# Motor_Driver.net
KiCad netlist of a schematic drawn in Altium Designer
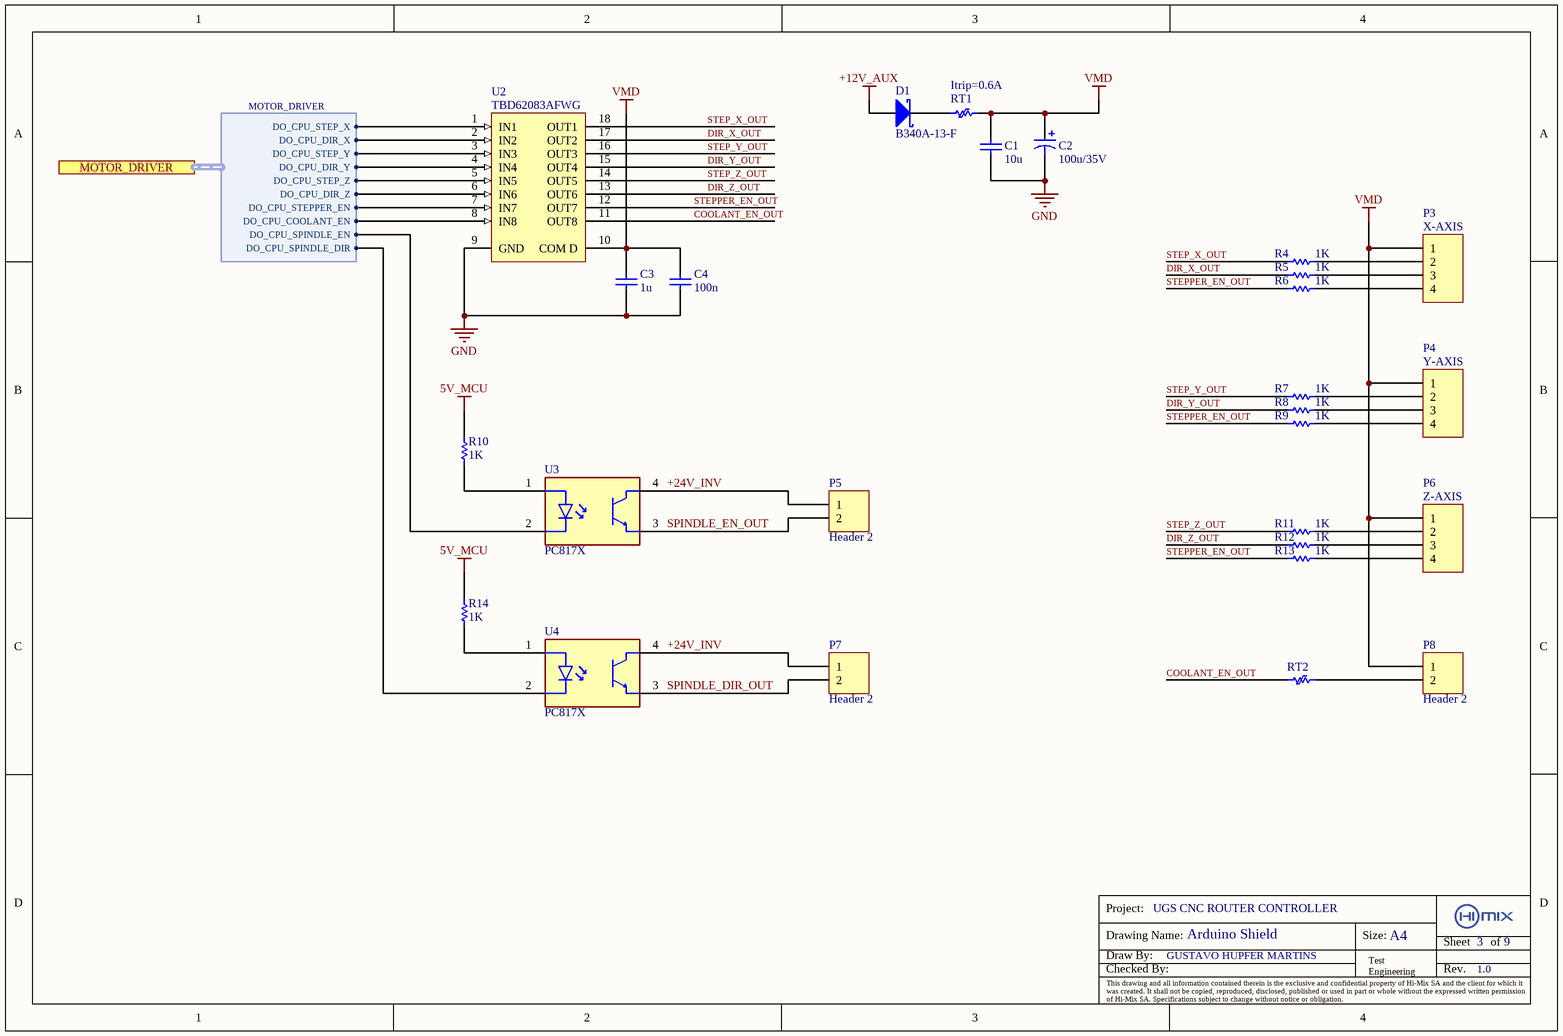
[diagram p0: Motor Driver.SchDoc]

(export (version "E")
  (design (tool "Eeschema 10.0.6"))
  (components
    (comp (ref "C1")
      (value "10u")
      (footprint "SMT1210_M")
      (description "Capacitor")
      (fields (field (name "Comment") "X7R/1210/50V") (field (name "PUBLISHER") "Altium Limited"))
      (libsource (lib "Miscellaneous Devices") (part "Cap"))
    )
    (comp (ref "C2")
      (value "100u/35V")
      (footprint "FKV Panasonic 8x10.2L (F)")
      (description "Polarized Capacitor (Radial)")
      (fields (field (name "Comment") "8x10.2"))
      (libsource (lib "Miscellaneous Devices") (part "Cap Pol1"))
    )
    (comp (ref "C3")
      (value "1u")
      (footprint "SMT0805_N")
      (description "Capacitor")
      (fields (field (name "Comment") "X7R/0805/50V") (field (name "PUBLISHER") "Altium Limited"))
      (libsource (lib "Miscellaneous Devices") (part "Cap"))
    )
    (comp (ref "C4")
      (value "100n")
      (footprint "SMT0603_N")
      (description "Capacitor")
      (fields (field (name "Comment") "X7R/0603/50V") (field (name "PUBLISHER") "Altium Limited"))
      (libsource (lib "Miscellaneous Devices") (part "Cap"))
    )
    (comp (ref "D1")
      (value "B340A-13-F")
      (footprint "SMB")
      (description "Schottky Diode")
      (libsource (lib "Miscellaneous Devices") (part "D Schottky"))
    )
    (comp (ref "P3")
      (value "~")
      (footprint "HDR1X4")
      (description "Header, 4-Pin")
      (fields (field (name "DESC.") "X-AXIS") (field (name "PUBLISHER") "Altium Limited"))
      (libsource (lib "Miscellaneous Connectors") (part "Header 4"))
    )
    (comp (ref "P4")
      (value "~")
      (footprint "HDR1X4")
      (description "Header, 4-Pin")
      (fields (field (name "DESC.") "Y-AXIS") (field (name "PUBLISHER") "Altium Limited"))
      (libsource (lib "Miscellaneous Connectors") (part "Header 4"))
    )
    (comp (ref "P5")
      (value "Header 2")
      (footprint "HDR1X2")
      (description "Header, 2-Pin")
      (fields (field (name "PUBLISHER") "Altium Limited"))
      (libsource (lib "Miscellaneous Connectors") (part "Header 2"))
    )
    (comp (ref "P6")
      (value "~")
      (footprint "HDR1X4")
      (description "Header, 4-Pin")
      (fields (field (name "DESC.") "Z-AXIS") (field (name "PUBLISHER") "Altium Limited"))
      (libsource (lib "Miscellaneous Connectors") (part "Header 4"))
    )
    (comp (ref "P7")
      (value "Header 2")
      (footprint "HDR1X2")
      (description "Header, 2-Pin")
      (fields (field (name "PUBLISHER") "Altium Limited"))
      (libsource (lib "Miscellaneous Connectors") (part "Header 2"))
    )
    (comp (ref "P8")
      (value "Header 2")
      (footprint "HDR1X2")
      (description "Header, 2-Pin")
      (fields (field (name "PUBLISHER") "Altium Limited"))
      (libsource (lib "Miscellaneous Connectors") (part "Header 2"))
    )
    (comp (ref "R4")
      (value "1K")
      (footprint "SMT1210_M")
      (description "Resistor")
      (fields (field (name "Comment") "1210/.5W/1Q") (field (name "PUBLISHER") "Altium Limited"))
      (libsource (lib "Miscellaneous Devices") (part "Res1"))
    )
    (comp (ref "R5")
      (value "1K")
      (footprint "SMT1210_M")
      (description "Resistor")
      (fields (field (name "Comment") "1210/.5W/1Q") (field (name "PUBLISHER") "Altium Limited"))
      (libsource (lib "Miscellaneous Devices") (part "Res1"))
    )
    (comp (ref "R6")
      (value "1K")
      (footprint "SMT1210_M")
      (description "Resistor")
      (fields (field (name "Comment") "1210/.5W/1Q") (field (name "PUBLISHER") "Altium Limited"))
      (libsource (lib "Miscellaneous Devices") (part "Res1"))
    )
    (comp (ref "R7")
      (value "1K")
      (footprint "SMT1210_M")
      (description "Resistor")
      (fields (field (name "Comment") "1210/.5W/1Q") (field (name "PUBLISHER") "Altium Limited"))
      (libsource (lib "Miscellaneous Devices") (part "Res1"))
    )
    (comp (ref "R8")
      (value "1K")
      (footprint "SMT1210_M")
      (description "Resistor")
      (fields (field (name "Comment") "1210/.5W/1Q") (field (name "PUBLISHER") "Altium Limited"))
      (libsource (lib "Miscellaneous Devices") (part "Res1"))
    )
    (comp (ref "R9")
      (value "1K")
      (footprint "SMT1210_M")
      (description "Resistor")
      (fields (field (name "Comment") "1210/.5W/1Q") (field (name "PUBLISHER") "Altium Limited"))
      (libsource (lib "Miscellaneous Devices") (part "Res1"))
    )
    (comp (ref "R10")
      (value "1K")
      (footprint "SMT1210_M")
      (description "Resistor")
      (fields (field (name "Comment") "1210/.5W/1Q") (field (name "PUBLISHER") "Altium Limited"))
      (libsource (lib "Miscellaneous Devices") (part "Res1"))
    )
    (comp (ref "R11")
      (value "1K")
      (footprint "SMT1210_M")
      (description "Resistor")
      (fields (field (name "Comment") "1210/.5W/1Q") (field (name "PUBLISHER") "Altium Limited"))
      (libsource (lib "Miscellaneous Devices") (part "Res1"))
    )
    (comp (ref "R12")
      (value "1K")
      (footprint "SMT1210_M")
      (description "Resistor")
      (fields (field (name "Comment") "1210/.5W/1Q") (field (name "PUBLISHER") "Altium Limited"))
      (libsource (lib "Miscellaneous Devices") (part "Res1"))
    )
    (comp (ref "R13")
      (value "1K")
      (footprint "SMT1210_M")
      (description "Resistor")
      (fields (field (name "Comment") "1210/.5W/1Q") (field (name "PUBLISHER") "Altium Limited"))
      (libsource (lib "Miscellaneous Devices") (part "Res1"))
    )
    (comp (ref "R14")
      (value "1K")
      (footprint "SMT1210_M")
      (description "Resistor")
      (fields (field (name "Comment") "1210/.5W/1Q") (field (name "PUBLISHER") "Altium Limited"))
      (libsource (lib "Miscellaneous Devices") (part "Res1"))
    )
    (comp (ref "RT1")
      (value "Itrip=0.6A")
      (footprint "AXIAL-0.2")
      (description "Thermistor")
      (fields (field (name "PUBLISHER") "Altium Limited"))
      (libsource (lib "Misc") (part "Poly Switch"))
    )
    (comp (ref "RT2")
      (value "Poly Switch")
      (footprint "AXIAL-0.2")
      (description "Thermistor")
      (fields (field (name "PUBLISHER") "Altium Limited"))
      (libsource (lib "Misc") (part "Poly Switch"))
    )
    (comp (ref "U2")
      (value "TBD62083AFWG")
      (footprint "SOIC18")
      (description "High-Voltage, High-Current Darlington Array")
      (libsource (lib "Allegro Interface Darlington Driver") (part "ULN2803LW"))
    )
    (comp (ref "U3")
      (value "PC817X")
      (footprint "DIP-4")
      (libsource (lib "ComponentLibrary") (part "PC817X"))
    )
    (comp (ref "U4")
      (value "PC817X")
      (footprint "DIP-4")
      (libsource (lib "ComponentLibrary") (part "PC817X"))
    )
  )
  (nets
    (net (code "2") (name "+12V_AUX") (class "Default")
      (node (ref "D1") (pin "1") (pinfunction "A_1") (pintype "passive"))
    )
    (net (code "3") (name "/+24V_INV") (class "Default")
      (node (ref "P5") (pin "1") (pinfunction "1_1") (pintype "passive"))
      (node (ref "P7") (pin "1") (pinfunction "1_1") (pintype "passive"))
      (node (ref "U3") (pin "4") (pinfunction "C_4") (pintype "passive"))
      (node (ref "U4") (pin "4") (pinfunction "C_4") (pintype "passive"))
    )
    (net (code "4") (name "/COOLANT_EN_OUT") (class "Default")
      (node (ref "RT2") (pin "1") (pinfunction "1_1") (pintype "passive"))
      (node (ref "U2") (pin "11") (pinfunction "OUT8_11") (pintype "open_collector"))
    )
    (net (code "5") (name "/DIR_X_OUT") (class "Default")
      (node (ref "R5") (pin "1") (pinfunction "1_1") (pintype "passive"))
      (node (ref "U2") (pin "17") (pinfunction "OUT2_17") (pintype "open_collector"))
    )
    (net (code "6") (name "/DIR_Y_OUT") (class "Default")
      (node (ref "R8") (pin "1") (pinfunction "1_1") (pintype "passive"))
      (node (ref "U2") (pin "15") (pinfunction "OUT4_15") (pintype "open_collector"))
    )
    (net (code "7") (name "/DIR_Z_OUT") (class "Default")
      (node (ref "R12") (pin "1") (pinfunction "1_1") (pintype "passive"))
      (node (ref "U2") (pin "13") (pinfunction "OUT6_13") (pintype "open_collector"))
    )
    (net (code "8") (name "/DO_CPU_COOLANT_EN") (class "Default")
      (node (ref "U2") (pin "8") (pinfunction "IN8_8") (pintype "input"))
    )
    (net (code "9") (name "/DO_CPU_DIR_X") (class "Default")
      (node (ref "U2") (pin "2") (pinfunction "IN2_2") (pintype "input"))
    )
    (net (code "10") (name "/DO_CPU_DIR_Y") (class "Default")
      (node (ref "U2") (pin "4") (pinfunction "IN4_4") (pintype "input"))
    )
    (net (code "11") (name "/DO_CPU_DIR_Z") (class "Default")
      (node (ref "U2") (pin "6") (pinfunction "IN6_6") (pintype "input"))
    )
    (net (code "12") (name "/DO_CPU_SPINDLE_DIR") (class "Default")
      (node (ref "U4") (pin "2") (pinfunction "K_2") (pintype "passive"))
    )
    (net (code "13") (name "/DO_CPU_SPINDLE_EN") (class "Default")
      (node (ref "U3") (pin "2") (pinfunction "K_2") (pintype "passive"))
    )
    (net (code "14") (name "/DO_CPU_STEPPER_EN") (class "Default")
      (node (ref "U2") (pin "7") (pinfunction "IN7_7") (pintype "input"))
    )
    (net (code "15") (name "/DO_CPU_STEP_X") (class "Default")
      (node (ref "U2") (pin "1") (pinfunction "IN1_1") (pintype "input"))
    )
    (net (code "16") (name "/DO_CPU_STEP_Y") (class "Default")
      (node (ref "U2") (pin "3") (pinfunction "IN3_3") (pintype "input"))
    )
    (net (code "17") (name "/DO_CPU_STEP_Z") (class "Default")
      (node (ref "U2") (pin "5") (pinfunction "IN5_5") (pintype "input"))
    )
    (net (code "18") (name "/SPINDLE_DIR_OUT") (class "Default")
      (node (ref "P7") (pin "2") (pinfunction "2_2") (pintype "passive"))
      (node (ref "U4") (pin "3") (pinfunction "E_3") (pintype "passive"))
    )
    (net (code "19") (name "/SPINDLE_EN_OUT") (class "Default")
      (node (ref "P5") (pin "2") (pinfunction "2_2") (pintype "passive"))
      (node (ref "U3") (pin "3") (pinfunction "E_3") (pintype "passive"))
    )
    (net (code "20") (name "/STEPPER_EN_OUT") (class "Default")
      (node (ref "R13") (pin "1") (pinfunction "1_1") (pintype "passive"))
      (node (ref "R6") (pin "1") (pinfunction "1_1") (pintype "passive"))
      (node (ref "R9") (pin "1") (pinfunction "1_1") (pintype "passive"))
      (node (ref "U2") (pin "12") (pinfunction "OUT7_12") (pintype "open_collector"))
    )
    (net (code "21") (name "/STEP_X_OUT") (class "Default")
      (node (ref "R4") (pin "1") (pinfunction "1_1") (pintype "passive"))
      (node (ref "U2") (pin "18") (pinfunction "OUT1_18") (pintype "open_collector"))
    )
    (net (code "22") (name "/STEP_Y_OUT") (class "Default")
      (node (ref "R7") (pin "1") (pinfunction "1_1") (pintype "passive"))
      (node (ref "U2") (pin "16") (pinfunction "OUT3_16") (pintype "open_collector"))
    )
    (net (code "23") (name "/STEP_Z_OUT") (class "Default")
      (node (ref "R11") (pin "1") (pinfunction "1_1") (pintype "passive"))
      (node (ref "U2") (pin "14") (pinfunction "OUT5_14") (pintype "open_collector"))
    )
    (net (code "25") (name "5V_MCU") (class "Default")
      (node (ref "R10") (pin "1") (pinfunction "1_1") (pintype "passive"))
      (node (ref "R14") (pin "1") (pinfunction "1_1") (pintype "passive"))
    )
    (net (code "26") (name "GND") (class "Default")
      (node (ref "C1") (pin "1") (pinfunction "1_1") (pintype "passive"))
      (node (ref "C2") (pin "2") (pinfunction "2_2") (pintype "passive"))
      (node (ref "C3") (pin "1") (pinfunction "1_1") (pintype "passive"))
      (node (ref "C4") (pin "1") (pinfunction "1_1") (pintype "passive"))
      (node (ref "U2") (pin "9") (pinfunction "GND_9") (pintype "power_in"))
    )
    (net (code "27") (name "Net-(D1-K)") (class "Default")
      (node (ref "D1") (pin "2") (pinfunction "K_2") (pintype "passive"))
      (node (ref "RT1") (pin "2") (pinfunction "2_2") (pintype "passive"))
    )
    (net (code "28") (name "Net-(P3-Pad2)") (class "Default")
      (node (ref "P3") (pin "2") (pinfunction "2_2") (pintype "passive"))
      (node (ref "R4") (pin "2") (pinfunction "2_2") (pintype "passive"))
    )
    (net (code "29") (name "Net-(P3-Pad3)") (class "Default")
      (node (ref "P3") (pin "3") (pinfunction "3_3") (pintype "passive"))
      (node (ref "R5") (pin "2") (pinfunction "2_2") (pintype "passive"))
    )
    (net (code "30") (name "Net-(P3-Pad4)") (class "Default")
      (node (ref "P3") (pin "4") (pinfunction "4_4") (pintype "passive"))
      (node (ref "R6") (pin "2") (pinfunction "2_2") (pintype "passive"))
    )
    (net (code "31") (name "Net-(P4-Pad2)") (class "Default")
      (node (ref "P4") (pin "2") (pinfunction "2_2") (pintype "passive"))
      (node (ref "R7") (pin "2") (pinfunction "2_2") (pintype "passive"))
    )
    (net (code "32") (name "Net-(P4-Pad3)") (class "Default")
      (node (ref "P4") (pin "3") (pinfunction "3_3") (pintype "passive"))
      (node (ref "R8") (pin "2") (pinfunction "2_2") (pintype "passive"))
    )
    (net (code "33") (name "Net-(P4-Pad4)") (class "Default")
      (node (ref "P4") (pin "4") (pinfunction "4_4") (pintype "passive"))
      (node (ref "R9") (pin "2") (pinfunction "2_2") (pintype "passive"))
    )
    (net (code "34") (name "Net-(P6-Pad2)") (class "Default")
      (node (ref "P6") (pin "2") (pinfunction "2_2") (pintype "passive"))
      (node (ref "R11") (pin "2") (pinfunction "2_2") (pintype "passive"))
    )
    (net (code "35") (name "Net-(P6-Pad3)") (class "Default")
      (node (ref "P6") (pin "3") (pinfunction "3_3") (pintype "passive"))
      (node (ref "R12") (pin "2") (pinfunction "2_2") (pintype "passive"))
    )
    (net (code "36") (name "Net-(P6-Pad4)") (class "Default")
      (node (ref "P6") (pin "4") (pinfunction "4_4") (pintype "passive"))
      (node (ref "R13") (pin "2") (pinfunction "2_2") (pintype "passive"))
    )
    (net (code "37") (name "Net-(P8-Pad2)") (class "Default")
      (node (ref "P8") (pin "2") (pinfunction "2_2") (pintype "passive"))
      (node (ref "RT2") (pin "2") (pinfunction "2_2") (pintype "passive"))
    )
    (net (code "38") (name "Net-(U3-A)") (class "Default")
      (node (ref "R10") (pin "2") (pinfunction "2_2") (pintype "passive"))
      (node (ref "U3") (pin "1") (pinfunction "A_1") (pintype "passive"))
    )
    (net (code "39") (name "Net-(U4-A)") (class "Default")
      (node (ref "R14") (pin "2") (pinfunction "2_2") (pintype "passive"))
      (node (ref "U4") (pin "1") (pinfunction "A_1") (pintype "passive"))
    )
    (net (code "40") (name "VMD") (class "Default")
      (node (ref "C1") (pin "2") (pinfunction "2_2") (pintype "passive"))
      (node (ref "C2") (pin "1") (pinfunction "1_1") (pintype "passive"))
      (node (ref "C3") (pin "2") (pinfunction "2_2") (pintype "passive"))
      (node (ref "C4") (pin "2") (pinfunction "2_2") (pintype "passive"))
      (node (ref "P3") (pin "1") (pinfunction "1_1") (pintype "passive"))
      (node (ref "P4") (pin "1") (pinfunction "1_1") (pintype "passive"))
      (node (ref "P6") (pin "1") (pinfunction "1_1") (pintype "passive"))
      (node (ref "P8") (pin "1") (pinfunction "1_1") (pintype "passive"))
      (node (ref "RT1") (pin "1") (pinfunction "1_1") (pintype "passive"))
      (node (ref "U2") (pin "10") (pinfunction "COM_D_10") (pintype "passive"))
    )
  )
)
